# POWER.net
KiCad netlist of a schematic drawn in Altium Designer
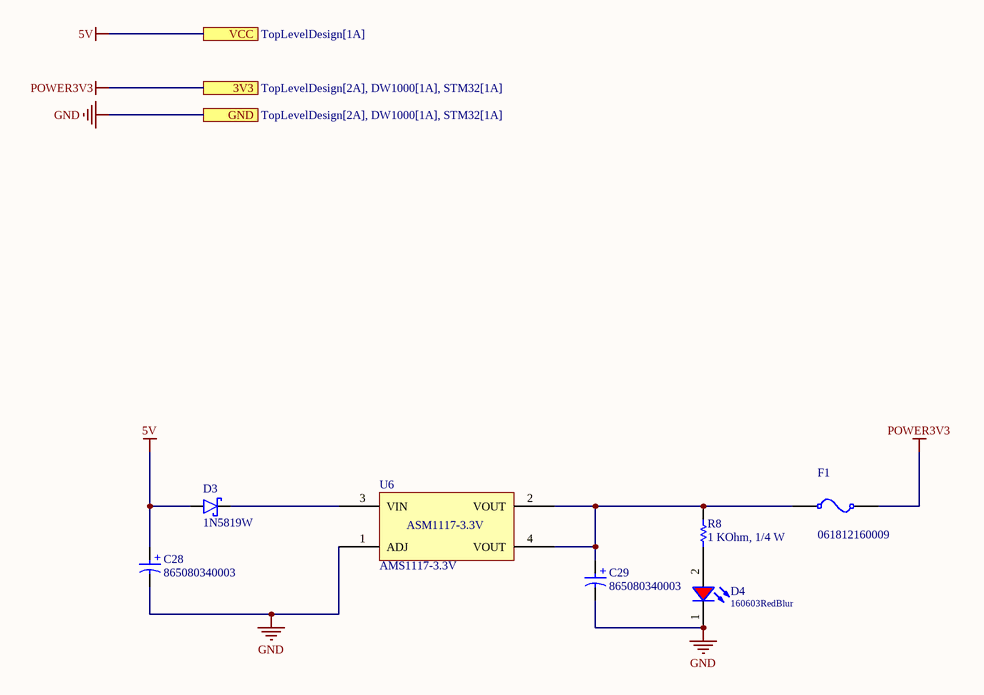
[diagram p0: POWER.SchDoc]

(export (version "E")
  (design (tool "Eeschema 10.0.6"))
  (components
    (comp (ref "C28")
      (value "865080340003")
      (footprint "WCAP-ASLI_D4H5.5")
      (description "V-Chip, D4 x H5.5mm, 22uF, 16V")
      (fields (field (name "MANUFACTURER") "Wurth Elektronik"))
      (libsource (lib "Tin Tran") (part "0710101508650801570160U20"))
    )
    (comp (ref "C29")
      (value "865080340003")
      (footprint "WCAP-ASLI_D4H5.5")
      (description "V-Chip, D4 x H5.5mm, 22uF, 16V")
      (fields (field (name "MANUFACTURER") "Wurth Elektronik"))
      (libsource (lib "Tin Tran") (part "0710101508650801570160U20"))
    )
    (comp (ref "D3") (value "1N5819W") (footprint "1N5819W") (libsource (lib "Tin Tran") (part "1N5819W")))
    (comp (ref "D4")
      (value "160603RedBlur")
      (footprint "WL-SMCW_0603_H=0.7mm")
      (description "WL-SMCW SMT Mono-color Chip LED Blur, size 0603, Red, 2V, 140deg")
      (libsource (lib "Tin Tran") (part "160603RedClear"))
    )
    (comp (ref "F1")
      (value "061812160009")
      (footprint "Fuse_SMD_1812")
      (description "Resettable Fuse, Size 1812, 9V, 1.6A")
      (fields (field (name "MANUFACTURER") "Littelfuse"))
      (libsource (lib "Tin Tran") (part "061812300006"))
    )
    (comp (ref "R8")
      (value "1 KOhm, 1/4 W")
      (footprint "resistor_0603")
      (description "RES, size 0603, 1 KOhm, 1/4 W")
      (fields (field (name "Comment") "0006031021"))
      (libsource (lib "Tin Tran") (part "00060371541"))
    )
    (comp (ref "U6")
      (value "AMS1117-3.3V")
      (footprint "AMS1117-3.3V SOT223")
      (description "AMS1117-3.3V, OUT 3.3V 1A.")
      (fields (field (name "MANUFACTURER") "AMS") (field (name "SOURCE") "AMS_family.SchLib"))
      (libsource (lib "Tin Tran") (part "AMS1117-3.3V"))
    )
  )
  (nets
    (net (code "1") (name "5V") (class "Default")
      (node (ref "C28") (pin "1") (pinfunction "P_1") (pintype "passive"))
      (node (ref "D3") (pin "A") (pinfunction "A_A") (pintype "passive"))
    )
    (net (code "2") (name "GND") (class "Default")
      (node (ref "C28") (pin "2") (pinfunction "N_2") (pintype "passive"))
      (node (ref "C29") (pin "2") (pinfunction "N_2") (pintype "passive"))
      (node (ref "D4") (pin "1") (pinfunction "K_1") (pintype "passive"))
      (node (ref "U6") (pin "1") (pinfunction "ADJ_1") (pintype "power_in"))
    )
    (net (code "3") (name "Net-(C29-P)") (class "Default")
      (node (ref "C29") (pin "1") (pinfunction "P_1") (pintype "passive"))
      (node (ref "F1") (pin "0") (pinfunction "0_0") (pintype "passive"))
      (node (ref "R8") (pin "2") (pinfunction "2_2") (pintype "passive"))
      (node (ref "U6") (pin "2") (pinfunction "VOUT_2") (pintype "passive"))
      (node (ref "U6") (pin "4") (pinfunction "VOUT_4") (pintype "power_in"))
    )
    (net (code "4") (name "Net-(D4-A)") (class "Default")
      (node (ref "D4") (pin "2") (pinfunction "A_2") (pintype "passive"))
      (node (ref "R8") (pin "1") (pinfunction "1_1") (pintype "passive"))
    )
    (net (code "5") (name "Net-(U6-VIN)") (class "Default")
      (node (ref "D3") (pin "K") (pinfunction "K_K") (pintype "passive"))
      (node (ref "U6") (pin "3") (pinfunction "VIN_3") (pintype "passive"))
    )
    (net (code "6") (name "POWER3V3") (class "Default")
      (node (ref "F1") (pin "1") (pinfunction "1_1") (pintype "passive"))
    )
  )
)
